# The_Flying_Jalapeno_v02.net
KiCad netlist of a schematic drawn in EAGLE
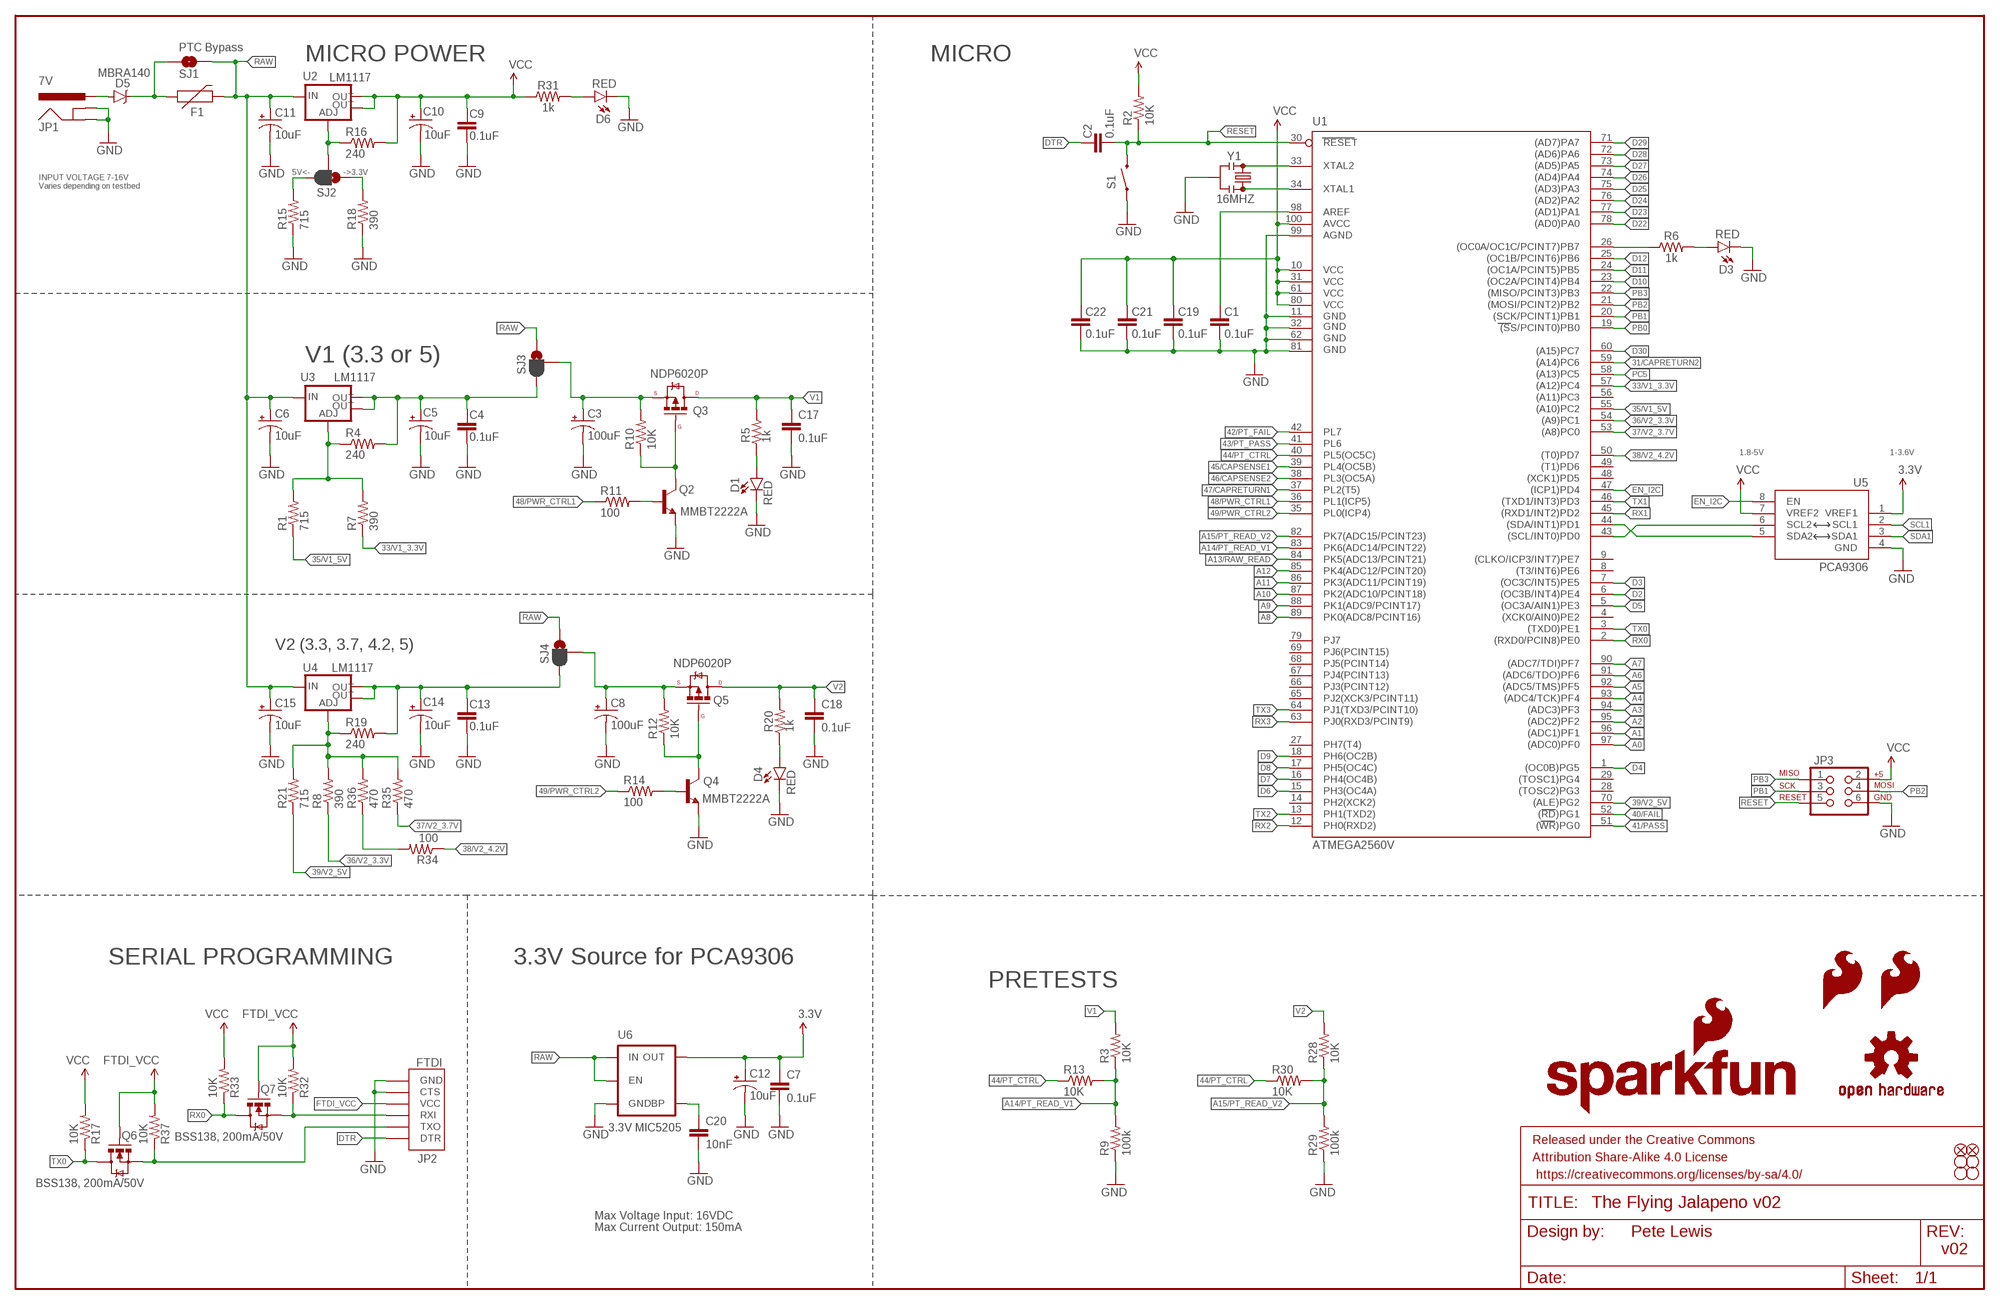
[diagram p0: schematic, sheet 1, part 1 of 2]
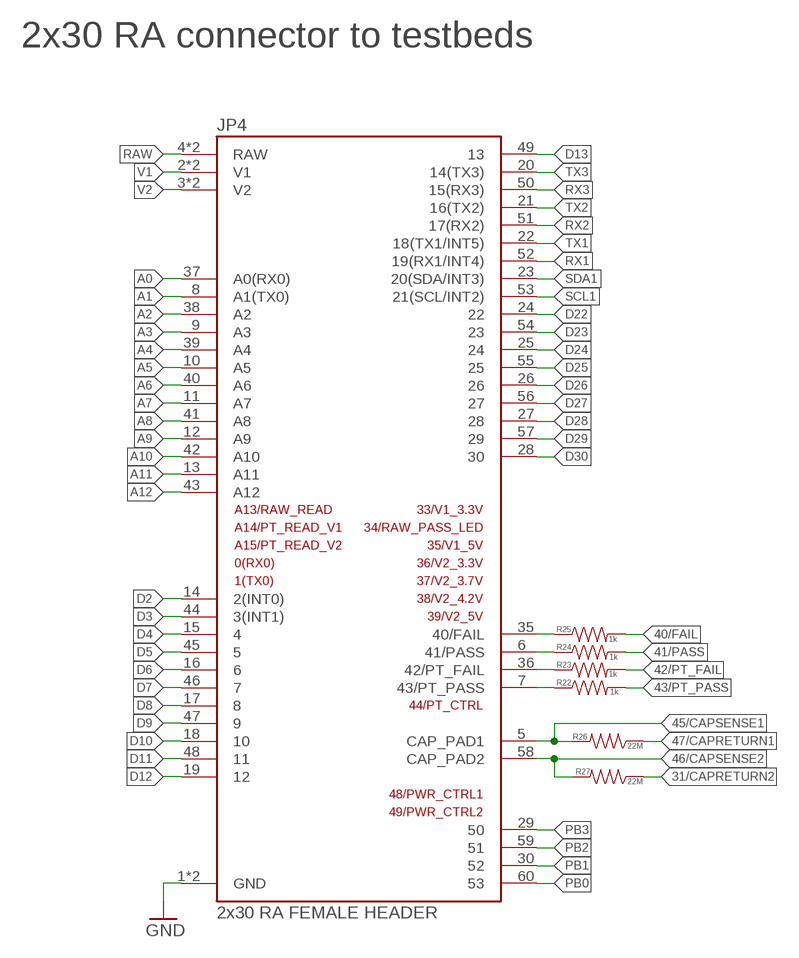
[diagram p1: schematic, sheet 1, part 2 of 2]

(export (version "E")
  (design (tool "Eeschema 10.0.6"))
  (components
    (comp (ref "C1")
      (value "0.1uF")
      (footprint "eagle-import:0603-CAP")
      (libsource (lib "eagle-import") (part "0.1UF-25V(+80/-20%)(0603)"))
    )
    (comp (ref "C2")
      (value "0.1uF")
      (footprint "eagle-import:0603-CAP")
      (libsource (lib "eagle-import") (part "0.1UF-25V(+80/-20%)(0603)"))
    )
    (comp (ref "C3")
      (value "100uF")
      (footprint "eagle-import:NIC_10X10.5_CAP")
      (libsource (lib "eagle-import") (part "100UF-63V-20%(ELECT)"))
    )
    (comp (ref "C4")
      (value "0.1uF")
      (footprint "eagle-import:0603-CAP")
      (libsource (lib "eagle-import") (part "0.1UF-25V(+80/-20%)(0603)"))
    )
    (comp (ref "C5")
      (value "10uF")
      (footprint "eagle-import:EIA3216")
      (libsource (lib "eagle-import") (part "10UF-16V-10%(TANT)"))
    )
    (comp (ref "C6")
      (value "10uF")
      (footprint "eagle-import:EIA3216")
      (libsource (lib "eagle-import") (part "10UF-16V-10%(TANT)"))
    )
    (comp (ref "C7")
      (value "0.1uF")
      (footprint "eagle-import:0603-CAP")
      (libsource (lib "eagle-import") (part "0.1UF-25V(+80/-20%)(0603)"))
    )
    (comp (ref "C8")
      (value "100uF")
      (footprint "eagle-import:NIC_10X10.5_CAP")
      (libsource (lib "eagle-import") (part "100UF-63V-20%(ELECT)"))
    )
    (comp (ref "C9")
      (value "0.1uF")
      (footprint "eagle-import:0603-CAP")
      (libsource (lib "eagle-import") (part "0.1UF-25V(+80/-20%)(0603)"))
    )
    (comp (ref "C10")
      (value "10uF")
      (footprint "eagle-import:EIA3216")
      (libsource (lib "eagle-import") (part "10UF-16V-10%(TANT)"))
    )
    (comp (ref "C11")
      (value "10uF")
      (footprint "eagle-import:EIA3216")
      (libsource (lib "eagle-import") (part "10UF-16V-10%(TANT)"))
    )
    (comp (ref "C12")
      (value "10uF")
      (footprint "eagle-import:0603-POL")
      (libsource (lib "eagle-import") (part "10UF-6.3V-20%(0603)(TANT){dblquote}"))
    )
    (comp (ref "C13")
      (value "0.1uF")
      (footprint "eagle-import:0603-CAP")
      (libsource (lib "eagle-import") (part "0.1UF-25V(+80/-20%)(0603)"))
    )
    (comp (ref "C14")
      (value "10uF")
      (footprint "eagle-import:EIA3216")
      (libsource (lib "eagle-import") (part "10UF-16V-10%(TANT)"))
    )
    (comp (ref "C15")
      (value "10uF")
      (footprint "eagle-import:EIA3216")
      (libsource (lib "eagle-import") (part "10UF-16V-10%(TANT)"))
    )
    (comp (ref "C17")
      (value "0.1uF")
      (footprint "eagle-import:0603-CAP")
      (libsource (lib "eagle-import") (part "0.1UF-25V(+80/-20%)(0603)"))
    )
    (comp (ref "C18")
      (value "0.1uF")
      (footprint "eagle-import:0603-CAP")
      (libsource (lib "eagle-import") (part "0.1UF-25V(+80/-20%)(0603)"))
    )
    (comp (ref "C19")
      (value "0.1uF")
      (footprint "eagle-import:0603-CAP")
      (libsource (lib "eagle-import") (part "0.1UF-25V(+80/-20%)(0603)"))
    )
    (comp (ref "C20")
      (value "10nF")
      (footprint "eagle-import:0603")
      (libsource (lib "eagle-import") (part "10NF-0603-50V-10%"))
    )
    (comp (ref "C21")
      (value "0.1uF")
      (footprint "eagle-import:0603-CAP")
      (libsource (lib "eagle-import") (part "0.1UF-25V(+80/-20%)(0603)"))
    )
    (comp (ref "C22")
      (value "0.1uF")
      (footprint "eagle-import:0603-CAP")
      (libsource (lib "eagle-import") (part "0.1UF-25V(+80/-20%)(0603)"))
    )
    (comp (ref "D1")
      (value "RED")
      (footprint "eagle-import:LED-1206")
      (libsource (lib "eagle-import") (part "LED-RED1206"))
    )
    (comp (ref "D3")
      (value "RED")
      (footprint "eagle-import:LED-1206")
      (libsource (lib "eagle-import") (part "LED-RED1206"))
    )
    (comp (ref "D4")
      (value "RED")
      (footprint "eagle-import:LED-1206")
      (libsource (lib "eagle-import") (part "LED-RED1206"))
    )
    (comp (ref "D5")
      (value "MBRA140")
      (footprint "eagle-import:SMA-DIODE")
      (libsource (lib "eagle-import") (part "DIODE-SCHOTTKY-MBRA140"))
    )
    (comp (ref "D6")
      (value "RED")
      (footprint "eagle-import:LED-1206")
      (libsource (lib "eagle-import") (part "LED-RED1206"))
    )
    (comp (ref "F1")
      (value "PTCTHERMISTOR1206")
      (footprint "eagle-import:PTC-1206")
      (libsource (lib "eagle-import") (part "PTCTHERMISTOR1206"))
    )
    (comp (ref "FRAME1")
      (value "FRAME-LEDGER")
      (footprint "eagle-import:CREATIVE_COMMONS")
      (libsource (lib "eagle-import") (part "FRAME-LEDGER"))
    )
    (comp (ref "JP1")
      (value "7V")
      (footprint "eagle-import:POWER_JACK_PTH_LOCK")
      (libsource (lib "eagle-import") (part "POWER_JACKPTH_LOCK"))
    )
    (comp (ref "JP2")
      (value "FTDI")
      (footprint "eagle-import:FTDI_DEVICE_RA_SMT")
      (libsource (lib "eagle-import") (part "FTDI_BASIC_DEVICE_SIDERA_SMT"))
    )
    (comp (ref "JP3")
      (value "AVR_SPI_PRG_6PTH")
      (footprint "eagle-import:2X3")
      (libsource (lib "eagle-import") (part "AVR_SPI_PRG_6PTH"))
    )
    (comp (ref "JP4")
      (value "2x30 RA FEMALE HEADER")
      (footprint "eagle-import:FLYING_JALAPENO_V2_F")
      (libsource (lib "eagle-import") (part "FLYING_JALAPENO_V2FEMALE"))
    )
    (comp (ref "JP5")
      (value "FIDUCIALUFIDUCIAL")
      (footprint "eagle-import:MICRO-FIDUCIAL")
      (libsource (lib "eagle-import") (part "FIDUCIALUFIDUCIAL"))
    )
    (comp (ref "JP8")
      (value "FIDUCIALUFIDUCIAL")
      (footprint "eagle-import:MICRO-FIDUCIAL")
      (libsource (lib "eagle-import") (part "FIDUCIALUFIDUCIAL"))
    )
    (comp (ref "LOGO1")
      (value "SFE_LOGO_NAME_FLAME.5_INCH")
      (footprint "eagle-import:SFE_LOGO_NAME_FLAME_.5")
      (libsource (lib "eagle-import") (part "SFE_LOGO_NAME_FLAME.5_INCH"))
    )
    (comp (ref "LOGO2")
      (value "SFE_LOGO_FLAME.3_INCH")
      (footprint "eagle-import:SFE_LOGO_FLAME_.3")
      (libsource (lib "eagle-import") (part "SFE_LOGO_FLAME.3_INCH"))
    )
    (comp (ref "LOGO3")
      (value "SFE_LOGO_FLAME.1_INCH")
      (footprint "eagle-import:SFE_LOGO_FLAME_.1")
      (libsource (lib "eagle-import") (part "SFE_LOGO_FLAME.1_INCH"))
    )
    (comp (ref "LOGO4")
      (value "OSHW-LOGOL")
      (footprint "eagle-import:OSHW-LOGO-L")
      (libsource (lib "eagle-import") (part "OSHW-LOGOL"))
    )
    (comp (ref "Q2")
      (value "MMBT2222A")
      (footprint "eagle-import:SOT23-3")
      (libsource (lib "eagle-import") (part "TRANSISTOR_NPNMMBT2222A"))
    )
    (comp (ref "Q3")
      (value "NDP6020P")
      (footprint "eagle-import:TO220V")
      (libsource (lib "eagle-import") (part "MOSFET-PCHANNELNDP6020P_20V_24A_LOW_VGS_TH"))
    )
    (comp (ref "Q4")
      (value "MMBT2222A")
      (footprint "eagle-import:SOT23-3")
      (libsource (lib "eagle-import") (part "TRANSISTOR_NPNMMBT2222A"))
    )
    (comp (ref "Q5")
      (value "NDP6020P")
      (footprint "eagle-import:TO220V")
      (libsource (lib "eagle-import") (part "MOSFET-PCHANNELNDP6020P_20V_24A_LOW_VGS_TH"))
    )
    (comp (ref "Q6")
      (value "BSS138, 200mA/50V")
      (footprint "eagle-import:SOT23-3")
      (libsource (lib "eagle-import") (part "MOSFET-NCHANNELBSS138"))
    )
    (comp (ref "Q7")
      (value "BSS138, 200mA/50V")
      (footprint "eagle-import:SOT23-3")
      (libsource (lib "eagle-import") (part "MOSFET-NCHANNELBSS138"))
    )
    (comp (ref "R1")
      (value "715")
      (footprint "eagle-import:0603-RES")
      (libsource (lib "eagle-import") (part "715OHM1/10W1%(0603)"))
    )
    (comp (ref "R2")
      (value "10K")
      (footprint "eagle-import:0603-RES")
      (libsource (lib "eagle-import") (part "10KOHM-1/10W-1%(0603)0603"))
    )
    (comp (ref "R3")
      (value "10K")
      (footprint "eagle-import:0603-RES")
      (libsource (lib "eagle-import") (part "10KOHM-1/10W-1%(0603)0603"))
    )
    (comp (ref "R4")
      (value "240")
      (footprint "eagle-import:0603-RES")
      (libsource (lib "eagle-import") (part "240OHM1/10W1%(0603)"))
    )
    (comp (ref "R5")
      (value "1k")
      (footprint "eagle-import:0603")
      (libsource (lib "eagle-import") (part "1KOHM-0603-1/10W-1%"))
    )
    (comp (ref "R6")
      (value "1k")
      (footprint "eagle-import:0603")
      (libsource (lib "eagle-import") (part "1KOHM-0603-1/10W-1%"))
    )
    (comp (ref "R7")
      (value "390")
      (footprint "eagle-import:0603-RES")
      (libsource (lib "eagle-import") (part "390OHM1/10W1%(0603)"))
    )
    (comp (ref "R8")
      (value "390")
      (footprint "eagle-import:0603-RES")
      (libsource (lib "eagle-import") (part "390OHM1/10W1%(0603)"))
    )
    (comp (ref "R9")
      (value "100k")
      (footprint "eagle-import:0603-RES")
      (libsource (lib "eagle-import") (part "100KOHM-1/10W-1%(0603)"))
    )
    (comp (ref "R10")
      (value "10K")
      (footprint "eagle-import:0603-RES")
      (libsource (lib "eagle-import") (part "10KOHM-1/10W-1%(0603)0603"))
    )
    (comp (ref "R11")
      (value "100")
      (footprint "eagle-import:0603-RES")
      (libsource (lib "eagle-import") (part "100OHM-1/10W-1%(0603)"))
    )
    (comp (ref "R12")
      (value "10K")
      (footprint "eagle-import:0603-RES")
      (libsource (lib "eagle-import") (part "10KOHM-1/10W-1%(0603)0603"))
    )
    (comp (ref "R13")
      (value "10K")
      (footprint "eagle-import:0603-RES")
      (libsource (lib "eagle-import") (part "10KOHM-1/10W-1%(0603)0603"))
    )
    (comp (ref "R14")
      (value "100")
      (footprint "eagle-import:0603-RES")
      (libsource (lib "eagle-import") (part "100OHM-1/10W-1%(0603)"))
    )
    (comp (ref "R15")
      (value "715")
      (footprint "eagle-import:0603-RES")
      (libsource (lib "eagle-import") (part "715OHM1/10W1%(0603)"))
    )
    (comp (ref "R16")
      (value "240")
      (footprint "eagle-import:0603-RES")
      (libsource (lib "eagle-import") (part "240OHM1/10W1%(0603)"))
    )
    (comp (ref "R17")
      (value "10K")
      (footprint "eagle-import:0603-RES")
      (libsource (lib "eagle-import") (part "10KOHM-1/10W-1%(0603)0603"))
    )
    (comp (ref "R18")
      (value "390")
      (footprint "eagle-import:0603-RES")
      (libsource (lib "eagle-import") (part "390OHM1/10W1%(0603)"))
    )
    (comp (ref "R19")
      (value "240")
      (footprint "eagle-import:0603-RES")
      (libsource (lib "eagle-import") (part "240OHM1/10W1%(0603)"))
    )
    (comp (ref "R20")
      (value "1k")
      (footprint "eagle-import:0603")
      (libsource (lib "eagle-import") (part "1KOHM-0603-1/10W-1%"))
    )
    (comp (ref "R21")
      (value "715")
      (footprint "eagle-import:0603-RES")
      (libsource (lib "eagle-import") (part "715OHM1/10W1%(0603)"))
    )
    (comp (ref "R22")
      (value "1k")
      (footprint "eagle-import:0603")
      (libsource (lib "eagle-import") (part "1KOHM-0603-1/10W-1%"))
    )
    (comp (ref "R23")
      (value "1k")
      (footprint "eagle-import:0603")
      (libsource (lib "eagle-import") (part "1KOHM-0603-1/10W-1%"))
    )
    (comp (ref "R24")
      (value "1k")
      (footprint "eagle-import:0603")
      (libsource (lib "eagle-import") (part "1KOHM-0603-1/10W-1%"))
    )
    (comp (ref "R25")
      (value "1k")
      (footprint "eagle-import:0603")
      (libsource (lib "eagle-import") (part "1KOHM-0603-1/10W-1%"))
    )
    (comp (ref "R26")
      (value "22M")
      (footprint "eagle-import:0603-RES")
      (libsource (lib "eagle-import") (part "22MOHM-1/10W-10%(0603)"))
    )
    (comp (ref "R27")
      (value "22M")
      (footprint "eagle-import:0603-RES")
      (libsource (lib "eagle-import") (part "22MOHM-1/10W-10%(0603)"))
    )
    (comp (ref "R28")
      (value "10K")
      (footprint "eagle-import:0603-RES")
      (libsource (lib "eagle-import") (part "10KOHM-1/10W-1%(0603)0603"))
    )
    (comp (ref "R29")
      (value "100k")
      (footprint "eagle-import:0603-RES")
      (libsource (lib "eagle-import") (part "100KOHM-1/10W-1%(0603)"))
    )
    (comp (ref "R30")
      (value "10K")
      (footprint "eagle-import:0603-RES")
      (libsource (lib "eagle-import") (part "10KOHM-1/10W-1%(0603)0603"))
    )
    (comp (ref "R31")
      (value "1k")
      (footprint "eagle-import:0603")
      (libsource (lib "eagle-import") (part "1KOHM-0603-1/10W-1%"))
    )
    (comp (ref "R32")
      (value "10K")
      (footprint "eagle-import:0603-RES")
      (libsource (lib "eagle-import") (part "10KOHM-1/10W-1%(0603)0603"))
    )
    (comp (ref "R33")
      (value "10K")
      (footprint "eagle-import:0603-RES")
      (libsource (lib "eagle-import") (part "10KOHM-1/10W-1%(0603)0603"))
    )
    (comp (ref "R34")
      (value "100")
      (footprint "eagle-import:0603-RES")
      (libsource (lib "eagle-import") (part "100OHM-1/10W-1%(0603)"))
    )
    (comp (ref "R35")
      (value "470")
      (footprint "eagle-import:0603-RES")
      (libsource (lib "eagle-import") (part "470OHM1/10W1%(0603)"))
    )
    (comp (ref "R36")
      (value "470")
      (footprint "eagle-import:0603-RES")
      (libsource (lib "eagle-import") (part "470OHM1/10W1%(0603)"))
    )
    (comp (ref "R37")
      (value "10K")
      (footprint "eagle-import:0603-RES")
      (libsource (lib "eagle-import") (part "10KOHM-1/10W-1%(0603)0603"))
    )
    (comp (ref "S1")
      (value "SWITCH-MOMENTARY-2SMD-REDUNDANT")
      (footprint "eagle-import:TACTILE-SWITCH-SMD")
      (libsource (lib "eagle-import") (part "SWITCH-MOMENTARY-2SMD-REDUNDANT"))
    )
    (comp (ref "SJ1")
      (value "PTC Bypass")
      (footprint "eagle-import:PAD-JUMPER-2-NO_NO_SILK")
      (libsource (lib "eagle-import") (part "JUMPER-PAD-2-NO"))
    )
    (comp (ref "SJ2")
      (value "JUMPER-PAD-3-2OF3_NC_BY_PASTE")
      (footprint "eagle-import:PAD-JUMPER-3-2OF3_NC_BY_PASTE_YES_SILK_FULL_BOX")
      (libsource (lib "eagle-import") (part "JUMPER-PAD-3-2OF3_NC_BY_PASTE"))
    )
    (comp (ref "SJ3")
      (value "JUMPER-PAD-3-2OF3_NC_BY_PASTE")
      (footprint "eagle-import:PAD-JUMPER-3-2OF3_NC_BY_PASTE_YES_SILK_FULL_BOX")
      (libsource (lib "eagle-import") (part "JUMPER-PAD-3-2OF3_NC_BY_PASTE"))
    )
    (comp (ref "SJ4")
      (value "JUMPER-PAD-3-2OF3_NC_BY_PASTE")
      (footprint "eagle-import:PAD-JUMPER-3-2OF3_NC_BY_PASTE_YES_SILK_FULL_BOX")
      (libsource (lib "eagle-import") (part "JUMPER-PAD-3-2OF3_NC_BY_PASTE"))
    )
    (comp (ref "STANDOFF1")
      (value "STAND-OFFTIGHT")
      (footprint "eagle-import:STAND-OFF-TIGHT")
      (libsource (lib "eagle-import") (part "STAND-OFFTIGHT"))
    )
    (comp (ref "STANDOFF2")
      (value "STAND-OFFTIGHT")
      (footprint "eagle-import:STAND-OFF-TIGHT")
      (libsource (lib "eagle-import") (part "STAND-OFFTIGHT"))
    )
    (comp (ref "STANDOFF3")
      (value "STAND-OFFTIGHT")
      (footprint "eagle-import:STAND-OFF-TIGHT")
      (libsource (lib "eagle-import") (part "STAND-OFFTIGHT"))
    )
    (comp (ref "STANDOFF4")
      (value "STAND-OFFTIGHT")
      (footprint "eagle-import:STAND-OFF-TIGHT")
      (libsource (lib "eagle-import") (part "STAND-OFFTIGHT"))
    )
    (comp (ref "U1")
      (value "ATMEGA2560AU")
      (footprint "eagle-import:TQFP100")
      (libsource (lib "eagle-import") (part "ATMEGA2560AU"))
    )
    (comp (ref "U2")
      (value "LM1117")
      (footprint "eagle-import:SOT223")
      (libsource (lib "eagle-import") (part "V_REG_LM1117SOT223"))
    )
    (comp (ref "U3")
      (value "LM1117")
      (footprint "eagle-import:SOT223")
      (libsource (lib "eagle-import") (part "V_REG_LM1117SOT223"))
    )
    (comp (ref "U4")
      (value "LM1117")
      (footprint "eagle-import:SOT223")
      (libsource (lib "eagle-import") (part "V_REG_LM1117SOT223"))
    )
    (comp (ref "U5")
      (value "PCA9306")
      (footprint "eagle-import:PCA9306DC-1_1")
      (libsource (lib "eagle-import") (part "PCA9306PCA9306DC-1{colon}1"))
    )
    (comp (ref "U6")
      (value "3.3V MIC5205")
      (footprint "eagle-import:SOT23-5")
      (libsource (lib "eagle-import") (part "MIC52053.3V"))
    )
    (comp (ref "Y1")
      (value "16MHZ")
      (footprint "eagle-import:RESONATOR-SMD")
      (libsource (lib "eagle-import") (part "RESONATOR16MHZ"))
    )
  )
  (nets
    (net (code "1") (name "3.3V") (class "Default")
      (node (ref "C12") (pin "A") (pinfunction "+_A") (pintype "passive"))
      (node (ref "C7") (pin "1") (pinfunction "1_1") (pintype "passive"))
      (node (ref "U5") (pin "1") (pinfunction "VREF1_1") (pintype "bidirectional"))
      (node (ref "U6") (pin "5") (pinfunction "OUT_5") (pintype "passive"))
    )
    (net (code "2") (name "31{slash}CAPRETURN2") (class "Default")
      (node (ref "R27") (pin "1") (pinfunction "1_1") (pintype "passive"))
      (node (ref "U1") (pin "59") (pinfunction "(A14)PC6_59") (pintype "bidirectional"))
    )
    (net (code "3") (name "33{slash}V1_3.3V") (class "Default")
      (node (ref "R7") (pin "1") (pinfunction "1_1") (pintype "passive"))
      (node (ref "U1") (pin "57") (pinfunction "(A12)PC4_57") (pintype "bidirectional"))
    )
    (net (code "4") (name "35{slash}V1_5V") (class "Default")
      (node (ref "R1") (pin "1") (pinfunction "1_1") (pintype "passive"))
      (node (ref "U1") (pin "55") (pinfunction "(A10)PC2_55") (pintype "bidirectional"))
    )
    (net (code "5") (name "36{slash}V2_3.3V") (class "Default")
      (node (ref "R8") (pin "1") (pinfunction "1_1") (pintype "passive"))
      (node (ref "U1") (pin "54") (pinfunction "(A9)PC1_54") (pintype "bidirectional"))
    )
    (net (code "6") (name "37{slash}V2_3.7V") (class "Default")
      (node (ref "R35") (pin "1") (pinfunction "1_1") (pintype "passive"))
      (node (ref "U1") (pin "53") (pinfunction "(A8)PC0_53") (pintype "bidirectional"))
    )
    (net (code "7") (name "38{slash}V2_4.2V") (class "Default")
      (node (ref "R34") (pin "1") (pinfunction "1_1") (pintype "passive"))
      (node (ref "U1") (pin "50") (pinfunction "(T0)PD7_50") (pintype "bidirectional"))
    )
    (net (code "8") (name "39{slash}V2_5V") (class "Default")
      (node (ref "R21") (pin "1") (pinfunction "1_1") (pintype "passive"))
      (node (ref "U1") (pin "70") (pinfunction "(ALE)PG2_70") (pintype "bidirectional"))
    )
    (net (code "9") (name "40{slash}FAIL") (class "Default")
      (node (ref "R25") (pin "2") (pinfunction "2_2") (pintype "passive"))
      (node (ref "U1") (pin "52") (pinfunction "(RD)PG1_52") (pintype "bidirectional"))
    )
    (net (code "10") (name "41{slash}PASS") (class "Default")
      (node (ref "R24") (pin "2") (pinfunction "2_2") (pintype "passive"))
      (node (ref "U1") (pin "51") (pinfunction "(WR)PG0_51") (pintype "bidirectional"))
    )
    (net (code "11") (name "42{slash}PT_FAIL") (class "Default")
      (node (ref "R23") (pin "2") (pinfunction "2_2") (pintype "passive"))
      (node (ref "U1") (pin "42") (pinfunction "PL7_42") (pintype "bidirectional"))
    )
    (net (code "12") (name "43{slash}PT_PASS") (class "Default")
      (node (ref "R22") (pin "2") (pinfunction "2_2") (pintype "passive"))
      (node (ref "U1") (pin "41") (pinfunction "PL6_41") (pintype "bidirectional"))
    )
    (net (code "13") (name "44{slash}PT_CTRL") (class "Default")
      (node (ref "R13") (pin "1") (pinfunction "1_1") (pintype "passive"))
      (node (ref "R30") (pin "1") (pinfunction "1_1") (pintype "passive"))
      (node (ref "U1") (pin "40") (pinfunction "PL5(OC5C)_40") (pintype "bidirectional"))
    )
    (net (code "14") (name "45{slash}CAPSENSE1") (class "Default")
      (node (ref "JP4") (pin "5") (pinfunction "CAP_PAD1_5") (pintype "bidirectional"))
      (node (ref "R26") (pin "2") (pinfunction "2_2") (pintype "passive"))
      (node (ref "U1") (pin "39") (pinfunction "PL4(OC5B)_39") (pintype "bidirectional"))
    )
    (net (code "15") (name "46{slash}CAPSENSE2") (class "Default")
      (node (ref "JP4") (pin "58") (pinfunction "CAP_PAD2_58") (pintype "bidirectional"))
      (node (ref "R27") (pin "2") (pinfunction "2_2") (pintype "passive"))
      (node (ref "U1") (pin "38") (pinfunction "PL3(OC5A)_38") (pintype "bidirectional"))
    )
    (net (code "16") (name "47{slash}CAPRETURN1") (class "Default")
      (node (ref "R26") (pin "1") (pinfunction "1_1") (pintype "passive"))
      (node (ref "U1") (pin "37") (pinfunction "PL2(T5)_37") (pintype "bidirectional"))
    )
    (net (code "17") (name "48{slash}PWR_CTRL1") (class "Default")
      (node (ref "R11") (pin "1") (pinfunction "1_1") (pintype "passive"))
      (node (ref "U1") (pin "36") (pinfunction "PL1(ICP5)_36") (pintype "bidirectional"))
    )
    (net (code "18") (name "49{slash}PWR_CTRL2") (class "Default")
      (node (ref "R14") (pin "1") (pinfunction "1_1") (pintype "passive"))
      (node (ref "U1") (pin "35") (pinfunction "PL0(ICP4)_35") (pintype "bidirectional"))
    )
    (net (code "19") (name "A0") (class "Default")
      (node (ref "JP4") (pin "37") (pinfunction "A0(RX0)_37") (pintype "bidirectional"))
      (node (ref "U1") (pin "97") (pinfunction "(ADC0)PF0_97") (pintype "bidirectional"))
    )
    (net (code "20") (name "A1") (class "Default")
      (node (ref "JP4") (pin "8") (pinfunction "A1(TX0)_8") (pintype "bidirectional"))
      (node (ref "U1") (pin "96") (pinfunction "(ADC1)PF1_96") (pintype "bidirectional"))
    )
    (net (code "21") (name "A2") (class "Default")
      (node (ref "JP4") (pin "38") (pinfunction "A2_38") (pintype "bidirectional"))
      (node (ref "U1") (pin "95") (pinfunction "(ADC2)PF2_95") (pintype "bidirectional"))
    )
    (net (code "22") (name "A3") (class "Default")
      (node (ref "JP4") (pin "9") (pinfunction "A3_9") (pintype "bidirectional"))
      (node (ref "U1") (pin "94") (pinfunction "(ADC3)PF3_94") (pintype "bidirectional"))
    )
    (net (code "23") (name "A4") (class "Default")
      (node (ref "JP4") (pin "39") (pinfunction "A4_39") (pintype "bidirectional"))
      (node (ref "U1") (pin "93") (pinfunction "(ADC4/TCK)PF4_93") (pintype "bidirectional"))
    )
    (net (code "24") (name "A5") (class "Default")
      (node (ref "JP4") (pin "10") (pinfunction "A5_10") (pintype "bidirectional"))
      (node (ref "U1") (pin "92") (pinfunction "(ADC5/TMS)PF5_92") (pintype "bidirectional"))
    )
    (net (code "25") (name "A6") (class "Default")
      (node (ref "JP4") (pin "40") (pinfunction "A6_40") (pintype "bidirectional"))
      (node (ref "U1") (pin "91") (pinfunction "(ADC6/TDO)PF6_91") (pintype "bidirectional"))
    )
    (net (code "26") (name "A7") (class "Default")
      (node (ref "JP4") (pin "11") (pinfunction "A7_11") (pintype "bidirectional"))
      (node (ref "U1") (pin "90") (pinfunction "(ADC7/TDI)PF7_90") (pintype "bidirectional"))
    )
    (net (code "27") (name "A8") (class "Default")
      (node (ref "JP4") (pin "41") (pinfunction "A8_41") (pintype "bidirectional"))
      (node (ref "U1") (pin "89") (pinfunction "PK0(ADC8/PCINT16)_89") (pintype "bidirectional"))
    )
    (net (code "28") (name "A9") (class "Default")
      (node (ref "JP4") (pin "12") (pinfunction "A9_12") (pintype "bidirectional"))
      (node (ref "U1") (pin "88") (pinfunction "PK1(ADC9/PCINT17)_88") (pintype "bidirectional"))
    )
    (net (code "29") (name "A10") (class "Default")
      (node (ref "JP4") (pin "42") (pinfunction "A10_42") (pintype "bidirectional"))
      (node (ref "U1") (pin "87") (pinfunction "PK2(ADC10/PCINT18)_87") (pintype "bidirectional"))
    )
    (net (code "30") (name "A11") (class "Default")
      (node (ref "JP4") (pin "13") (pinfunction "A11_13") (pintype "bidirectional"))
      (node (ref "U1") (pin "86") (pinfunction "PK3(ADC11/PCINT19)_86") (pintype "bidirectional"))
    )
    (net (code "31") (name "A12") (class "Default")
      (node (ref "JP4") (pin "43") (pinfunction "A12_43") (pintype "bidirectional"))
      (node (ref "U1") (pin "85") (pinfunction "PK4(ADC12/PCINT20)_85") (pintype "bidirectional"))
    )
    (net (code "32") (name "A13{slash}RAW_READ") (class "Default")
      (node (ref "U1") (pin "84") (pinfunction "PK5(ADC13/PCINT21)_84") (pintype "bidirectional"))
    )
    (net (code "33") (name "A14{slash}PT_READ_V1") (class "Default")
      (node (ref "R13") (pin "2") (pinfunction "2_2") (pintype "passive"))
      (node (ref "R3") (pin "1") (pinfunction "1_1") (pintype "passive"))
      (node (ref "R9") (pin "2") (pinfunction "2_2") (pintype "passive"))
      (node (ref "U1") (pin "83") (pinfunction "PK6(ADC14/PCINT22)_83") (pintype "bidirectional"))
    )
    (net (code "34") (name "A15{slash}PT_READ_V2") (class "Default")
      (node (ref "R28") (pin "1") (pinfunction "1_1") (pintype "passive"))
      (node (ref "R29") (pin "2") (pinfunction "2_2") (pintype "passive"))
      (node (ref "R30") (pin "2") (pinfunction "2_2") (pintype "passive"))
      (node (ref "U1") (pin "82") (pinfunction "PK7(ADC15/PCINT23)_82") (pintype "bidirectional"))
    )
    (net (code "35") (name "D2") (class "Default")
      (node (ref "JP4") (pin "14") (pinfunction "2(INT0)_14") (pintype "bidirectional"))
      (node (ref "U1") (pin "6") (pinfunction "(OC3B/INT4)PE4_6") (pintype "bidirectional"))
    )
    (net (code "36") (name "D3") (class "Default")
      (node (ref "JP4") (pin "44") (pinfunction "3(INT1)_44") (pintype "bidirectional"))
      (node (ref "U1") (pin "7") (pinfunction "(OC3C/INT5)PE5_7") (pintype "bidirectional"))
    )
    (net (code "37") (name "D4") (class "Default")
      (node (ref "JP4") (pin "15") (pinfunction "4_15") (pintype "bidirectional"))
      (node (ref "U1") (pin "1") (pinfunction "(OC0B)PG5_1") (pintype "bidirectional"))
    )
    (net (code "38") (name "D5") (class "Default")
      (node (ref "JP4") (pin "45") (pinfunction "5_45") (pintype "bidirectional"))
      (node (ref "U1") (pin "5") (pinfunction "(OC3A/AIN1)PE3_5") (pintype "bidirectional"))
    )
    (net (code "39") (name "D6") (class "Default")
      (node (ref "JP4") (pin "16") (pinfunction "6_16") (pintype "bidirectional"))
      (node (ref "U1") (pin "15") (pinfunction "PH3(OC4A)_15") (pintype "bidirectional"))
    )
    (net (code "40") (name "D7") (class "Default")
      (node (ref "JP4") (pin "46") (pinfunction "7_46") (pintype "bidirectional"))
      (node (ref "U1") (pin "16") (pinfunction "PH4(OC4B)_16") (pintype "bidirectional"))
    )
    (net (code "41") (name "D8") (class "Default")
      (node (ref "JP4") (pin "17") (pinfunction "8_17") (pintype "bidirectional"))
      (node (ref "U1") (pin "17") (pinfunction "PH5(OC4C)_17") (pintype "bidirectional"))
    )
    (net (code "42") (name "D9") (class "Default")
      (node (ref "JP4") (pin "47") (pinfunction "9_47") (pintype "bidirectional"))
      (node (ref "U1") (pin "18") (pinfunction "PH6(OC2B)_18") (pintype "bidirectional"))
    )
    (net (code "43") (name "D10") (class "Default")
      (node (ref "JP4") (pin "18") (pinfunction "10_18") (pintype "bidirectional"))
      (node (ref "U1") (pin "23") (pinfunction "(OC2A/PCINT4)PB4_23") (pintype "bidirectional"))
    )
    (net (code "44") (name "D11") (class "Default")
      (node (ref "JP4") (pin "48") (pinfunction "11_48") (pintype "bidirectional"))
      (node (ref "U1") (pin "24") (pinfunction "(OC1A/PCINT5)PB5_24") (pintype "bidirectional"))
    )
    (net (code "45") (name "D12") (class "Default")
      (node (ref "JP4") (pin "19") (pinfunction "12_19") (pintype "bidirectional"))
      (node (ref "U1") (pin "25") (pinfunction "(OC1B/PCINT6)PB6_25") (pintype "bidirectional"))
    )
    (net (code "46") (name "D13") (class "Default")
      (node (ref "JP4") (pin "49") (pinfunction "13_49") (pintype "bidirectional"))
      (node (ref "R6") (pin "1") (pinfunction "1_1") (pintype "passive"))
      (node (ref "U1") (pin "26") (pinfunction "(OC0A/OC1C/PCINT7)PB7_26") (pintype "bidirectional"))
    )
    (net (code "47") (name "D22") (class "Default")
      (node (ref "JP4") (pin "24") (pinfunction "22_24") (pintype "bidirectional"))
      (node (ref "U1") (pin "78") (pinfunction "(AD0)PA0_78") (pintype "bidirectional"))
    )
    (net (code "48") (name "D23") (class "Default")
      (node (ref "JP4") (pin "54") (pinfunction "23_54") (pintype "bidirectional"))
      (node (ref "U1") (pin "77") (pinfunction "(AD1)PA1_77") (pintype "bidirectional"))
    )
    (net (code "49") (name "D24") (class "Default")
      (node (ref "JP4") (pin "25") (pinfunction "24_25") (pintype "bidirectional"))
      (node (ref "U1") (pin "76") (pinfunction "(AD2)PA2_76") (pintype "bidirectional"))
    )
    (net (code "50") (name "D25") (class "Default")
      (node (ref "JP4") (pin "55") (pinfunction "25_55") (pintype "bidirectional"))
      (node (ref "U1") (pin "75") (pinfunction "(AD3)PA3_75") (pintype "bidirectional"))
    )
    (net (code "51") (name "D26") (class "Default")
      (node (ref "JP4") (pin "26") (pinfunction "26_26") (pintype "bidirectional"))
      (node (ref "U1") (pin "74") (pinfunction "(AD4)PA4_74") (pintype "bidirectional"))
    )
    (net (code "52") (name "D27") (class "Default")
      (node (ref "JP4") (pin "56") (pinfunction "27_56") (pintype "bidirectional"))
      (node (ref "U1") (pin "73") (pinfunction "(AD5)PA5_73") (pintype "bidirectional"))
    )
    (net (code "53") (name "D28") (class "Default")
      (node (ref "JP4") (pin "27") (pinfunction "28_27") (pintype "bidirectional"))
      (node (ref "U1") (pin "72") (pinfunction "(AD6)PA6_72") (pintype "bidirectional"))
    )
    (net (code "54") (name "D29") (class "Default")
      (node (ref "JP4") (pin "57") (pinfunction "29_57") (pintype "bidirectional"))
      (node (ref "U1") (pin "71") (pinfunction "(AD7)PA7_71") (pintype "bidirectional"))
    )
    (net (code "55") (name "D30") (class "Default")
      (node (ref "JP4") (pin "28") (pinfunction "30_28") (pintype "bidirectional"))
      (node (ref "U1") (pin "60") (pinfunction "(A15)PC7_60") (pintype "bidirectional"))
    )
    (net (code "56") (name "DTR") (class "Default")
      (node (ref "C2") (pin "2") (pinfunction "2_2") (pintype "passive"))
      (node (ref "JP2") (pin "1") (pinfunction "DTR_1") (pintype "bidirectional"))
    )
    (net (code "57") (name "EN_I2C") (class "Default")
      (node (ref "U1") (pin "47") (pinfunction "(ICP1)PD4_47") (pintype "bidirectional"))
      (node (ref "U5") (pin "8") (pinfunction "EN_8") (pintype "bidirectional"))
    )
    (net (code "58") (name "FTDI_VCC") (class "Default")
      (node (ref "JP2") (pin "4") (pinfunction "VCC_4") (pintype "bidirectional"))
      (node (ref "Q6") (pin "1") (pinfunction "G_1") (pintype "passive"))
      (node (ref "Q7") (pin "1") (pinfunction "G_1") (pintype "passive"))
      (node (ref "R32") (pin "2") (pinfunction "2_2") (pintype "passive"))
      (node (ref "R37") (pin "2") (pinfunction "2_2") (pintype "passive"))
    )
    (net (code "59") (name "GND") (class "Default")
      (node (ref "C1") (pin "1") (pinfunction "1_1") (pintype "passive"))
      (node (ref "C10") (pin "C") (pinfunction "-_C") (pintype "passive"))
      (node (ref "C11") (pin "C") (pinfunction "-_C") (pintype "passive"))
      (node (ref "C12") (pin "K") (pinfunction "-_K") (pintype "passive"))
      (node (ref "C13") (pin "2") (pinfunction "2_2") (pintype "passive"))
      (node (ref "C14") (pin "C") (pinfunction "-_C") (pintype "passive"))
      (node (ref "C15") (pin "C") (pinfunction "-_C") (pintype "passive"))
      (node (ref "C17") (pin "2") (pinfunction "2_2") (pintype "passive"))
      (node (ref "C18") (pin "2") (pinfunction "2_2") (pintype "passive"))
      (node (ref "C19") (pin "1") (pinfunction "1_1") (pintype "passive"))
      (node (ref "C20") (pin "2") (pinfunction "2_2") (pintype "passive"))
      (node (ref "C21") (pin "1") (pinfunction "1_1") (pintype "passive"))
      (node (ref "C22") (pin "1") (pinfunction "1_1") (pintype "passive"))
      (node (ref "C3") (pin "-") (pinfunction "-_-") (pintype "passive"))
      (node (ref "C4") (pin "2") (pinfunction "2_2") (pintype "passive"))
      (node (ref "C5") (pin "C") (pinfunction "-_C") (pintype "passive"))
      (node (ref "C6") (pin "C") (pinfunction "-_C") (pintype "passive"))
      (node (ref "C7") (pin "2") (pinfunction "2_2") (pintype "passive"))
      (node (ref "C8") (pin "-") (pinfunction "-_-") (pintype "passive"))
      (node (ref "C9") (pin "2") (pinfunction "2_2") (pintype "passive"))
      (node (ref "D1") (pin "C") (pinfunction "C_C") (pintype "passive"))
      (node (ref "D3") (pin "C") (pinfunction "C_C") (pintype "passive"))
      (node (ref "D4") (pin "C") (pinfunction "C_C") (pintype "passive"))
      (node (ref "D6") (pin "C") (pinfunction "C_C") (pintype "passive"))
      (node (ref "JP1") (pin "GND") (pinfunction "GND_GND") (pintype "bidirectional"))
      (node (ref "JP1") (pin "GNDBREAK") (pinfunction "GNDBREAK_GNDBREAK") (pintype "bidirectional"))
      (node (ref "JP2") (pin "5") (pinfunction "CTS_5") (pintype "bidirectional"))
      (node (ref "JP2") (pin "6") (pinfunction "GND_6") (pintype "bidirectional"))
      (node (ref "JP3") (pin "6") (pinfunction "6_6") (pintype "passive"))
      (node (ref "JP4") (pin "1") (pinfunction "GND_1") (pintype "bidirectional"))
      (node (ref "JP4") (pin "31") (pinfunction "GND_31") (pintype "bidirectional"))
      (node (ref "Q2") (pin "2") (pinfunction "E_2") (pintype "passive"))
      (node (ref "Q4") (pin "2") (pinfunction "E_2") (pintype "passive"))
      (node (ref "R15") (pin "1") (pinfunction "1_1") (pintype "passive"))
      (node (ref "R18") (pin "1") (pinfunction "1_1") (pintype "passive"))
      (node (ref "R29") (pin "1") (pinfunction "1_1") (pintype "passive"))
      (node (ref "R9") (pin "1") (pinfunction "1_1") (pintype "passive"))
      (node (ref "S1") (pin "1") (pinfunction "1_1") (pintype "passive"))
      (node (ref "S1") (pin "2") (pinfunction "1_2") (pintype "passive"))
      (node (ref "U1") (pin "11") (pinfunction "GND_11") (pintype "power_in"))
      (node (ref "U1") (pin "32") (pinfunction "GND1_32") (pintype "power_in"))
      (node (ref "U1") (pin "62") (pinfunction "GND2_62") (pintype "power_in"))
      (node (ref "U1") (pin "81") (pinfunction "GND3_81") (pintype "power_in"))
      (node (ref "U1") (pin "99") (pinfunction "AGND_99") (pintype "power_in"))
      (node (ref "U5") (pin "4") (pinfunction "GND_4") (pintype "bidirectional"))
      (node (ref "U6") (pin "2") (pinfunction "GND_2") (pintype "input"))
      (node (ref "Y1") (pin "2") (pinfunction "2_2") (pintype "passive"))
    )
    (net (code "60") (name "Net-(C5-+)") (class "Default")
      (node (ref "C4") (pin "1") (pinfunction "1_1") (pintype "passive"))
      (node (ref "C5") (pin "A") (pinfunction "+_A") (pintype "passive"))
      (node (ref "R4") (pin "2") (pinfunction "2_2") (pintype "passive"))
      (node (ref "SJ3") (pin "3") (pinfunction "3_3") (pintype "passive"))
      (node (ref "U3") (pin "2") (pinfunction "OUT_2") (pintype "output"))
      (node (ref "U3") (pin "4") (pinfunction "OUT_4") (pintype "output"))
    )
    (net (code "61") (name "Net-(C14-+)") (class "Default")
      (node (ref "C13") (pin "1") (pinfunction "1_1") (pintype "passive"))
      (node (ref "C14") (pin "A") (pinfunction "+_A") (pintype "passive"))
      (node (ref "R19") (pin "2") (pinfunction "2_2") (pintype "passive"))
      (node (ref "SJ4") (pin "3") (pinfunction "3_3") (pintype "passive"))
      (node (ref "U4") (pin "2") (pinfunction "OUT_2") (pintype "output"))
      (node (ref "U4") (pin "4") (pinfunction "OUT_4") (pintype "output"))
    )
    (net (code "62") (name "Net-(D1-PadA)") (class "Default")
      (node (ref "D1") (pin "A") (pinfunction "A_A") (pintype "passive"))
      (node (ref "R5") (pin "1") (pinfunction "1_1") (pintype "passive"))
    )
    (net (code "63") (name "Net-(D3-PadA)") (class "Default")
      (node (ref "D3") (pin "A") (pinfunction "A_A") (pintype "passive"))
      (node (ref "R6") (pin "2") (pinfunction "2_2") (pintype "passive"))
    )
    (net (code "64") (name "Net-(D4-PadA)") (class "Default")
      (node (ref "D4") (pin "A") (pinfunction "A_A") (pintype "passive"))
      (node (ref "R20") (pin "1") (pinfunction "1_1") (pintype "passive"))
    )
    (net (code "65") (name "Net-(D5-PadA)") (class "Default")
      (node (ref "D5") (pin "A") (pinfunction "A_A") (pintype "passive"))
      (node (ref "JP1") (pin "PWR") (pinfunction "PWR_PWR") (pintype "bidirectional"))
    )
    (net (code "66") (name "Net-(D5-PadC)") (class "Default")
      (node (ref "D5") (pin "C") (pinfunction "C_C") (pintype "passive"))
      (node (ref "F1") (pin "1") (pinfunction "1_1") (pintype "bidirectional"))
      (node (ref "SJ1") (pin "1") (pinfunction "1_1") (pintype "passive"))
    )
    (net (code "67") (name "Net-(D6-PadA)") (class "Default")
      (node (ref "D6") (pin "A") (pinfunction "A_A") (pintype "passive"))
      (node (ref "R31") (pin "2") (pinfunction "2_2") (pintype "passive"))
    )
    (net (code "68") (name "Net-(JP2-RXI)") (class "Default")
      (node (ref "JP2") (pin "3") (pinfunction "RXI_3") (pintype "bidirectional"))
      (node (ref "Q7") (pin "2") (pinfunction "S_2") (pintype "passive"))
      (node (ref "R32") (pin "1") (pinfunction "1_1") (pintype "passive"))
    )
    (net (code "69") (name "Net-(JP2-TXO)") (class "Default")
      (node (ref "JP2") (pin "2") (pinfunction "TXO_2") (pintype "bidirectional"))
      (node (ref "Q6") (pin "2") (pinfunction "S_2") (pintype "passive"))
      (node (ref "R37") (pin "1") (pinfunction "1_1") (pintype "passive"))
    )
    (net (code "70") (name "Net-(JP4-40{slash}FAIL)") (class "Default")
      (node (ref "JP4") (pin "35") (pinfunction "40/FAIL_35") (pintype "bidirectional"))
      (node (ref "R25") (pin "1") (pinfunction "1_1") (pintype "passive"))
    )
    (net (code "71") (name "Net-(JP4-41{slash}PASS)") (class "Default")
      (node (ref "JP4") (pin "6") (pinfunction "41/PASS_6") (pintype "bidirectional"))
      (node (ref "R24") (pin "1") (pinfunction "1_1") (pintype "passive"))
    )
    (net (code "72") (name "Net-(JP4-42{slash}PT_FAIL)") (class "Default")
      (node (ref "JP4") (pin "36") (pinfunction "42/PT_FAIL_36") (pintype "bidirectional"))
      (node (ref "R23") (pin "1") (pinfunction "1_1") (pintype "passive"))
    )
    (net (code "73") (name "Net-(JP4-43{slash}PT_PASS)") (class "Default")
      (node (ref "JP4") (pin "7") (pinfunction "43/PT_PASS_7") (pintype "bidirectional"))
      (node (ref "R22") (pin "1") (pinfunction "1_1") (pintype "passive"))
    )
    (net (code "74") (name "Net-(Q2-B)") (class "Default")
      (node (ref "Q2") (pin "1") (pinfunction "B_1") (pintype "passive"))
      (node (ref "R11") (pin "2") (pinfunction "2_2") (pintype "passive"))
    )
    (net (code "75") (name "Net-(Q2-C)") (class "Default")
      (node (ref "Q2") (pin "3") (pinfunction "C_3") (pintype "passive"))
      (node (ref "Q3") (pin "1") (pinfunction "G_1") (pintype "passive"))
      (node (ref "R10") (pin "1") (pinfunction "1_1") (pintype "passive"))
    )
    (net (code "76") (name "Net-(Q3-S)") (class "Default")
      (node (ref "C3") (pin "+") (pinfunction "+_+") (pintype "passive"))
      (node (ref "Q3") (pin "3") (pinfunction "S_3") (pintype "passive"))
      (node (ref "R10") (pin "2") (pinfunction "2_2") (pintype "passive"))
      (node (ref "SJ3") (pin "2") (pinfunction "2_2") (pintype "passive"))
    )
    (net (code "77") (name "Net-(Q4-B)") (class "Default")
      (node (ref "Q4") (pin "1") (pinfunction "B_1") (pintype "passive"))
      (node (ref "R14") (pin "2") (pinfunction "2_2") (pintype "passive"))
    )
    (net (code "78") (name "Net-(Q4-C)") (class "Default")
      (node (ref "Q4") (pin "3") (pinfunction "C_3") (pintype "passive"))
      (node (ref "Q5") (pin "1") (pinfunction "G_1") (pintype "passive"))
      (node (ref "R12") (pin "1") (pinfunction "1_1") (pintype "passive"))
    )
    (net (code "79") (name "Net-(Q5-S)") (class "Default")
      (node (ref "C8") (pin "+") (pinfunction "+_+") (pintype "passive"))
      (node (ref "Q5") (pin "3") (pinfunction "S_3") (pintype "passive"))
      (node (ref "R12") (pin "2") (pinfunction "2_2") (pintype "passive"))
      (node (ref "SJ4") (pin "2") (pinfunction "2_2") (pintype "passive"))
    )
    (net (code "80") (name "Net-(R15-Pad2)") (class "Default")
      (node (ref "R15") (pin "2") (pinfunction "2_2") (pintype "passive"))
      (node (ref "SJ2") (pin "3") (pinfunction "3_3") (pintype "passive"))
    )
    (net (code "81") (name "Net-(R18-Pad2)") (class "Default")
      (node (ref "R18") (pin "2") (pinfunction "2_2") (pintype "passive"))
      (node (ref "SJ2") (pin "1") (pinfunction "1_1") (pintype "passive"))
    )
    (net (code "82") (name "Net-(R34-Pad2)") (class "Default")
      (node (ref "R34") (pin "2") (pinfunction "2_2") (pintype "passive"))
      (node (ref "R36") (pin "1") (pinfunction "1_1") (pintype "passive"))
    )
    (net (code "83") (name "Net-(U1-(SCL{slash}INT0)PD0)") (class "Default")
      (node (ref "U1") (pin "43") (pinfunction "(SCL/INT0)PD0_43") (pintype "bidirectional"))
      (node (ref "U5") (pin "6") (pinfunction "SCL2_6") (pintype "bidirectional"))
    )
    (net (code "84") (name "Net-(U1-(SDA{slash}INT1)PD1)") (class "Default")
      (node (ref "U1") (pin "44") (pinfunction "(SDA/INT1)PD1_44") (pintype "bidirectional"))
      (node (ref "U5") (pin "5") (pinfunction "SDA2_5") (pintype "bidirectional"))
    )
    (net (code "85") (name "Net-(U1-AREF)") (class "Default")
      (node (ref "C1") (pin "2") (pinfunction "2_2") (pintype "passive"))
      (node (ref "U1") (pin "98") (pinfunction "AREF_98") (pintype "bidirectional"))
    )
    (net (code "86") (name "Net-(U1-XTAL1)") (class "Default")
      (node (ref "U1") (pin "34") (pinfunction "XTAL1_34") (pintype "input"))
      (node (ref "Y1") (pin "1") (pinfunction "1_1") (pintype "passive"))
    )
    (net (code "87") (name "Net-(U1-XTAL2)") (class "Default")
      (node (ref "U1") (pin "33") (pinfunction "XTAL2_33") (pintype "output"))
      (node (ref "Y1") (pin "3") (pinfunction "3_3") (pintype "passive"))
    )
    (net (code "88") (name "Net-(U2-ADJ)") (class "Default")
      (node (ref "R16") (pin "1") (pinfunction "1_1") (pintype "passive"))
      (node (ref "SJ2") (pin "2") (pinfunction "2_2") (pintype "passive"))
      (node (ref "U2") (pin "1") (pinfunction "ADJ_1") (pintype "input"))
    )
    (net (code "89") (name "Net-(U3-ADJ)") (class "Default")
      (node (ref "R1") (pin "2") (pinfunction "2_2") (pintype "passive"))
      (node (ref "R4") (pin "1") (pinfunction "1_1") (pintype "passive"))
      (node (ref "R7") (pin "2") (pinfunction "2_2") (pintype "passive"))
      (node (ref "U3") (pin "1") (pinfunction "ADJ_1") (pintype "input"))
    )
    (net (code "90") (name "Net-(U4-ADJ)") (class "Default")
      (node (ref "R19") (pin "1") (pinfunction "1_1") (pintype "passive"))
      (node (ref "R21") (pin "2") (pinfunction "2_2") (pintype "passive"))
      (node (ref "R35") (pin "2") (pinfunction "2_2") (pintype "passive"))
      (node (ref "R36") (pin "2") (pinfunction "2_2") (pintype "passive"))
      (node (ref "R8") (pin "2") (pinfunction "2_2") (pintype "passive"))
      (node (ref "U4") (pin "1") (pinfunction "ADJ_1") (pintype "input"))
    )
    (net (code "91") (name "Net-(U6-BP)") (class "Default")
      (node (ref "C20") (pin "1") (pinfunction "1_1") (pintype "passive"))
      (node (ref "U6") (pin "4") (pinfunction "BP_4") (pintype "input"))
    )
    (net (code "92") (name "PB0") (class "Default")
      (node (ref "JP4") (pin "60") (pinfunction "53_60") (pintype "bidirectional"))
      (node (ref "U1") (pin "19") (pinfunction "(SS/PCINT0)PB0_19") (pintype "bidirectional"))
    )
    (net (code "93") (name "PB1") (class "Default")
      (node (ref "JP3") (pin "3") (pinfunction "3_3") (pintype "passive"))
      (node (ref "JP4") (pin "30") (pinfunction "52_30") (pintype "bidirectional"))
      (node (ref "U1") (pin "20") (pinfunction "(SCK/PCINT1)PB1_20") (pintype "bidirectional"))
    )
    (net (code "94") (name "PB2") (class "Default")
      (node (ref "JP3") (pin "4") (pinfunction "4_4") (pintype "passive"))
      (node (ref "JP4") (pin "59") (pinfunction "51_59") (pintype "bidirectional"))
      (node (ref "U1") (pin "21") (pinfunction "(MOSI/PCINT2)PB2_21") (pintype "bidirectional"))
    )
    (net (code "95") (name "PB3") (class "Default")
      (node (ref "JP3") (pin "1") (pinfunction "1_1") (pintype "passive"))
      (node (ref "JP4") (pin "29") (pinfunction "50_29") (pintype "bidirectional"))
      (node (ref "U1") (pin "22") (pinfunction "(MISO/PCINT3)PB3_22") (pintype "bidirectional"))
    )
    (net (code "96") (name "PC5") (class "Default")
      (node (ref "U1") (pin "58") (pinfunction "(A13)PC5_58") (pintype "bidirectional"))
    )
    (net (code "97") (name "RAW") (class "Default")
      (node (ref "C11") (pin "A") (pinfunction "+_A") (pintype "passive"))
      (node (ref "C15") (pin "A") (pinfunction "+_A") (pintype "passive"))
      (node (ref "C6") (pin "A") (pinfunction "+_A") (pintype "passive"))
      (node (ref "F1") (pin "2") (pinfunction "2_2") (pintype "bidirectional"))
      (node (ref "JP4") (pin "34") (pinfunction "RAW_34") (pintype "bidirectional"))
      (node (ref "JP4") (pin "4") (pinfunction "RAW_4") (pintype "bidirectional"))
      (node (ref "SJ1") (pin "2") (pinfunction "2_2") (pintype "passive"))
      (node (ref "SJ3") (pin "1") (pinfunction "1_1") (pintype "passive"))
      (node (ref "SJ4") (pin "1") (pinfunction "1_1") (pintype "passive"))
      (node (ref "U2") (pin "3") (pinfunction "IN_3") (pintype "input"))
      (node (ref "U3") (pin "3") (pinfunction "IN_3") (pintype "input"))
      (node (ref "U4") (pin "3") (pinfunction "IN_3") (pintype "input"))
      (node (ref "U6") (pin "1") (pinfunction "IN_1") (pintype "input"))
      (node (ref "U6") (pin "3") (pinfunction "EN_3") (pintype "input"))
    )
    (net (code "98") (name "RESET") (class "Default")
      (node (ref "C2") (pin "1") (pinfunction "1_1") (pintype "passive"))
      (node (ref "JP3") (pin "5") (pinfunction "5_5") (pintype "passive"))
      (node (ref "R2") (pin "1") (pinfunction "1_1") (pintype "passive"))
      (node (ref "S1") (pin "3") (pinfunction "2_3") (pintype "passive"))
      (node (ref "S1") (pin "4") (pinfunction "2_4") (pintype "passive"))
      (node (ref "U1") (pin "30") (pinfunction "RESET_30") (pintype "input"))
    )
    (net (code "99") (name "RX0") (class "Default")
      (node (ref "Q7") (pin "3") (pinfunction "D_3") (pintype "passive"))
      (node (ref "R33") (pin "1") (pinfunction "1_1") (pintype "passive"))
      (node (ref "U1") (pin "2") (pinfunction "(RXD0/PCIN8)PE0_2") (pintype "bidirectional"))
    )
    (net (code "100") (name "RX1") (class "Default")
      (node (ref "JP4") (pin "52") (pinfunction "19(RX1/INT4)_52") (pintype "bidirectional"))
      (node (ref "U1") (pin "45") (pinfunction "(RXD1/INT2)PD2_45") (pintype "bidirectional"))
    )
    (net (code "101") (name "RX2") (class "Default")
      (node (ref "JP4") (pin "51") (pinfunction "17(RX2)_51") (pintype "bidirectional"))
      (node (ref "U1") (pin "12") (pinfunction "PH0(RXD2)_12") (pintype "bidirectional"))
    )
    (net (code "102") (name "RX3") (class "Default")
      (node (ref "JP4") (pin "50") (pinfunction "15(RX3)_50") (pintype "bidirectional"))
      (node (ref "U1") (pin "63") (pinfunction "PJ0(RXD3/PCINT9)_63") (pintype "bidirectional"))
    )
    (net (code "103") (name "SCL1") (class "Default")
      (node (ref "JP4") (pin "53") (pinfunction "21(SCL/INT2)_53") (pintype "bidirectional"))
      (node (ref "U5") (pin "2") (pinfunction "SCL1_2") (pintype "bidirectional"))
    )
    (net (code "104") (name "SDA1") (class "Default")
      (node (ref "JP4") (pin "23") (pinfunction "20(SDA/INT3)_23") (pintype "bidirectional"))
      (node (ref "U5") (pin "3") (pinfunction "SDA1_3") (pintype "bidirectional"))
    )
    (net (code "105") (name "TX0") (class "Default")
      (node (ref "Q6") (pin "3") (pinfunction "D_3") (pintype "passive"))
      (node (ref "R17") (pin "1") (pinfunction "1_1") (pintype "passive"))
      (node (ref "U1") (pin "3") (pinfunction "(TXD0)PE1_3") (pintype "bidirectional"))
    )
    (net (code "106") (name "TX1") (class "Default")
      (node (ref "JP4") (pin "22") (pinfunction "18(TX1/INT5)_22") (pintype "bidirectional"))
      (node (ref "U1") (pin "46") (pinfunction "(TXD1/INT3)PD3_46") (pintype "bidirectional"))
    )
    (net (code "107") (name "TX2") (class "Default")
      (node (ref "JP4") (pin "21") (pinfunction "16(TX2)_21") (pintype "bidirectional"))
      (node (ref "U1") (pin "13") (pinfunction "PH1(TXD2)_13") (pintype "bidirectional"))
    )
    (net (code "108") (name "TX3") (class "Default")
      (node (ref "JP4") (pin "20") (pinfunction "14(TX3)_20") (pintype "bidirectional"))
      (node (ref "U1") (pin "64") (pinfunction "PJ1(TXD3/PCINT10)_64") (pintype "bidirectional"))
    )
    (net (code "109") (name "V1") (class "Default")
      (node (ref "C17") (pin "1") (pinfunction "1_1") (pintype "passive"))
      (node (ref "JP4") (pin "2") (pinfunction "V1_2") (pintype "bidirectional"))
      (node (ref "JP4") (pin "32") (pinfunction "V1_32") (pintype "bidirectional"))
      (node (ref "Q3") (pin "2") (pinfunction "D_2") (pintype "passive"))
      (node (ref "R3") (pin "2") (pinfunction "2_2") (pintype "passive"))
      (node (ref "R5") (pin "2") (pinfunction "2_2") (pintype "passive"))
    )
    (net (code "110") (name "V2") (class "Default")
      (node (ref "C18") (pin "1") (pinfunction "1_1") (pintype "passive"))
      (node (ref "JP4") (pin "3") (pinfunction "V2_3") (pintype "bidirectional"))
      (node (ref "JP4") (pin "33") (pinfunction "V2_33") (pintype "bidirectional"))
      (node (ref "Q5") (pin "2") (pinfunction "D_2") (pintype "passive"))
      (node (ref "R20") (pin "2") (pinfunction "2_2") (pintype "passive"))
      (node (ref "R28") (pin "2") (pinfunction "2_2") (pintype "passive"))
    )
    (net (code "111") (name "VCC") (class "Default")
      (node (ref "C10") (pin "A") (pinfunction "+_A") (pintype "passive"))
      (node (ref "C19") (pin "2") (pinfunction "2_2") (pintype "passive"))
      (node (ref "C21") (pin "2") (pinfunction "2_2") (pintype "passive"))
      (node (ref "C22") (pin "2") (pinfunction "2_2") (pintype "passive"))
      (node (ref "C9") (pin "1") (pinfunction "1_1") (pintype "passive"))
      (node (ref "JP3") (pin "2") (pinfunction "2_2") (pintype "passive"))
      (node (ref "R16") (pin "2") (pinfunction "2_2") (pintype "passive"))
      (node (ref "R17") (pin "2") (pinfunction "2_2") (pintype "passive"))
      (node (ref "R2") (pin "2") (pinfunction "2_2") (pintype "passive"))
      (node (ref "R31") (pin "1") (pinfunction "1_1") (pintype "passive"))
      (node (ref "R33") (pin "2") (pinfunction "2_2") (pintype "passive"))
      (node (ref "U1") (pin "10") (pinfunction "VCC_10") (pintype "power_in"))
      (node (ref "U1") (pin "100") (pinfunction "AVCC_100") (pintype "power_in"))
      (node (ref "U1") (pin "31") (pinfunction "VCC1_31") (pintype "power_in"))
      (node (ref "U1") (pin "61") (pinfunction "VCC2_61") (pintype "power_in"))
      (node (ref "U1") (pin "80") (pinfunction "VCC3_80") (pintype "power_in"))
      (node (ref "U2") (pin "2") (pinfunction "OUT_2") (pintype "output"))
      (node (ref "U2") (pin "4") (pinfunction "OUT_4") (pintype "output"))
      (node (ref "U5") (pin "7") (pinfunction "VREF2_7") (pintype "bidirectional"))
    )
    (net (code "112") (name "unconnected-(U1-(A11)PC3-Pad56)") (class "Default")
      (node (ref "U1") (pin "56") (pinfunction "(A11)PC3_56") (pintype "bidirectional"))
    )
    (net (code "113") (name "unconnected-(U1-(CLKO{slash}ICP3{slash}INT7)PE7-Pad9)") (class "Default")
      (node (ref "U1") (pin "9") (pinfunction "(CLKO/ICP3/INT7)PE7_9") (pintype "bidirectional"))
    )
    (net (code "114") (name "unconnected-(U1-(T1)PD6-Pad49)") (class "Default")
      (node (ref "U1") (pin "49") (pinfunction "(T1)PD6_49") (pintype "bidirectional"))
    )
    (net (code "115") (name "unconnected-(U1-(T3{slash}INT6)PE6-Pad8)") (class "Default")
      (node (ref "U1") (pin "8") (pinfunction "(T3/INT6)PE6_8") (pintype "bidirectional"))
    )
    (net (code "116") (name "unconnected-(U1-(TOSC1)PG4-Pad29)") (class "Default")
      (node (ref "U1") (pin "29") (pinfunction "(TOSC1)PG4_29") (pintype "bidirectional"))
    )
    (net (code "117") (name "unconnected-(U1-(TOSC2)PG3-Pad28)") (class "Default")
      (node (ref "U1") (pin "28") (pinfunction "(TOSC2)PG3_28") (pintype "bidirectional"))
    )
    (net (code "118") (name "unconnected-(U1-(XCK0{slash}AIN0)PE2-Pad4)") (class "Default")
      (node (ref "U1") (pin "4") (pinfunction "(XCK0/AIN0)PE2_4") (pintype "bidirectional"))
    )
    (net (code "119") (name "unconnected-(U1-(XCK1)PD5-Pad48)") (class "Default")
      (node (ref "U1") (pin "48") (pinfunction "(XCK1)PD5_48") (pintype "bidirectional"))
    )
    (net (code "120") (name "unconnected-(U1-PH2(XCK2)-Pad14)") (class "Default")
      (node (ref "U1") (pin "14") (pinfunction "PH2(XCK2)_14") (pintype "bidirectional"))
    )
    (net (code "121") (name "unconnected-(U1-PH7(T4)-Pad27)") (class "Default")
      (node (ref "U1") (pin "27") (pinfunction "PH7(T4)_27") (pintype "bidirectional"))
    )
    (net (code "122") (name "unconnected-(U1-PJ2(XCK3{slash}PCINT11)-Pad65)") (class "Default")
      (node (ref "U1") (pin "65") (pinfunction "PJ2(XCK3/PCINT11)_65") (pintype "bidirectional"))
    )
    (net (code "123") (name "unconnected-(U1-PJ3(PCINT12)-Pad66)") (class "Default")
      (node (ref "U1") (pin "66") (pinfunction "PJ3(PCINT12)_66") (pintype "bidirectional"))
    )
    (net (code "124") (name "unconnected-(U1-PJ4(PCINT13)-Pad67)") (class "Default")
      (node (ref "U1") (pin "67") (pinfunction "PJ4(PCINT13)_67") (pintype "bidirectional"))
    )
    (net (code "125") (name "unconnected-(U1-PJ5(PCINT14)-Pad68)") (class "Default")
      (node (ref "U1") (pin "68") (pinfunction "PJ5(PCINT14)_68") (pintype "bidirectional"))
    )
    (net (code "126") (name "unconnected-(U1-PJ6(PCINT15)-Pad69)") (class "Default")
      (node (ref "U1") (pin "69") (pinfunction "PJ6(PCINT15)_69") (pintype "bidirectional"))
    )
    (net (code "127") (name "unconnected-(U1-PJ7-Pad79)") (class "Default")
      (node (ref "U1") (pin "79") (pinfunction "PJ7_79") (pintype "bidirectional"))
    )
  )
)
